# CH32V20xG8-R0.net
KiCad netlist of a schematic drawn in Altium Designer
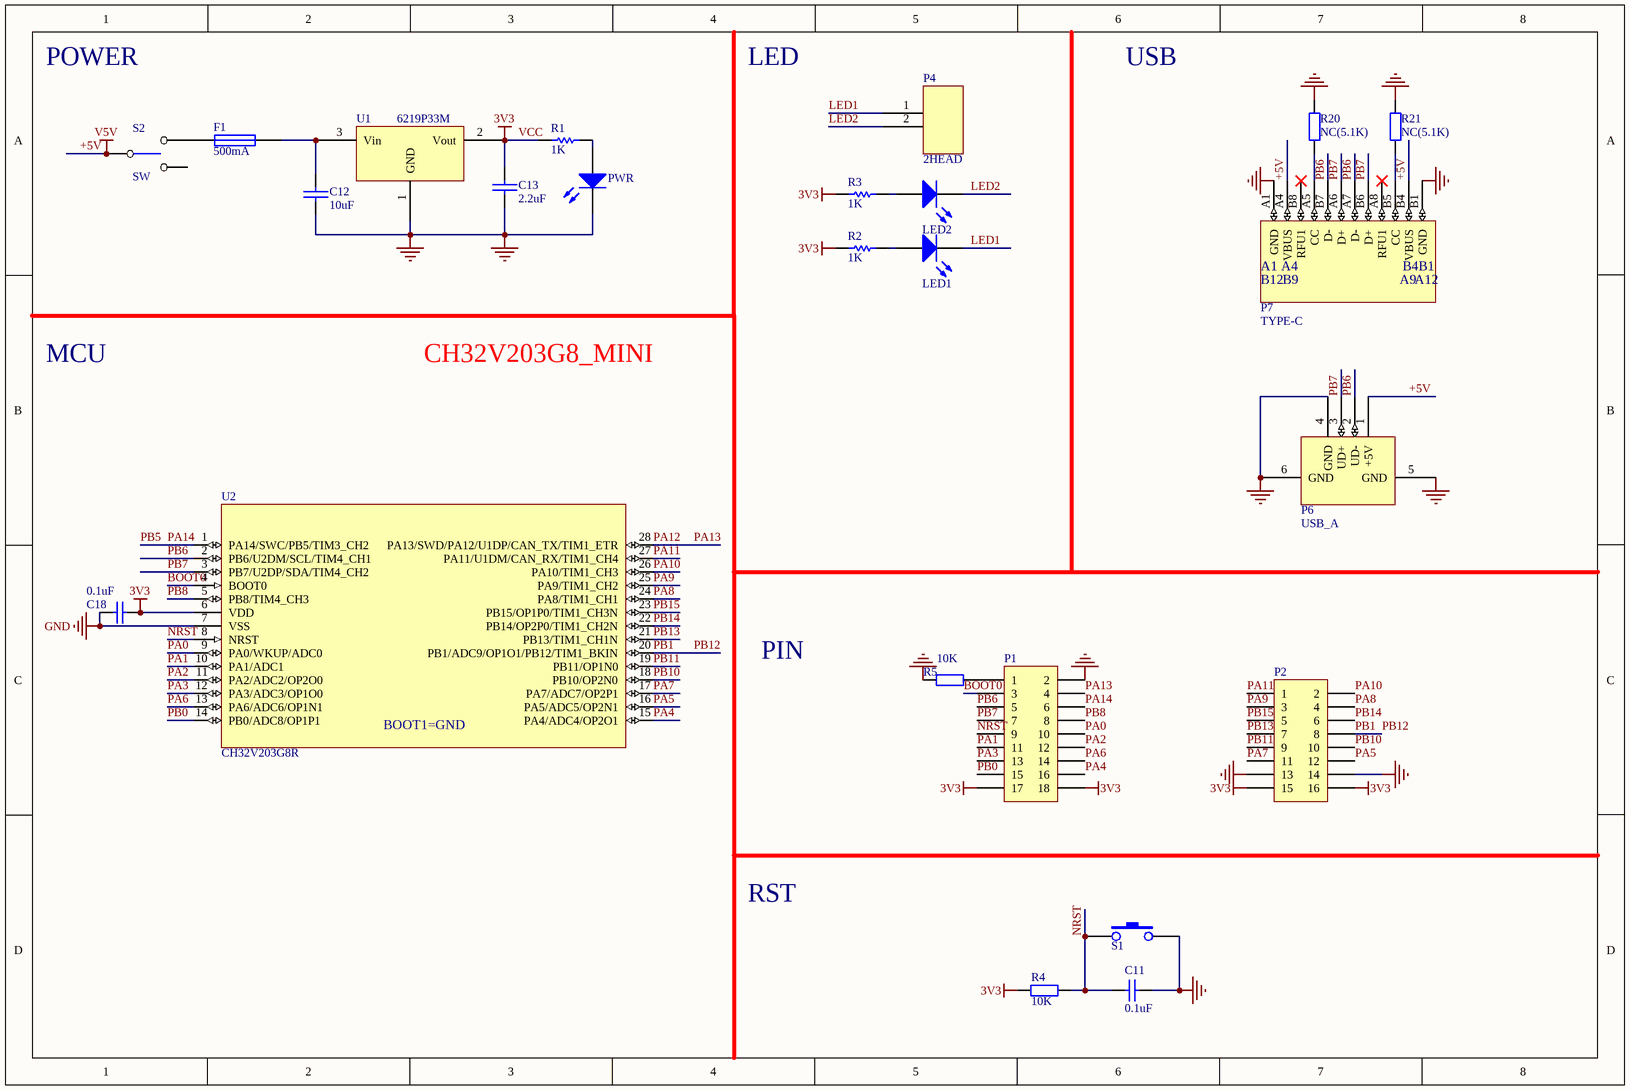
[diagram p0: CH32V20xG8-R0.SchDoc]

(export (version "E")
  (design (tool "Eeschema 10.0.6"))
  (components
    (comp (ref "C11")
      (value "0.1uF")
      (footprint "0603_C")
      (description "Capacitor")
      (fields (field (name "PUBLISHER") "Altium Limited"))
      (libsource (lib "*") (part "Cap"))
    )
    (comp (ref "C12")
      (value "10uF")
      (footprint "3216_C")
      (description "Capacitor")
      (libsource (lib "wch_sch_others") (part "CAP"))
    )
    (comp (ref "C13")
      (value "2.2uF")
      (footprint "0603_C")
      (description "Capacitor")
      (libsource (lib "wch_sch_others") (part "CAP"))
    )
    (comp (ref "C18")
      (value "0.1uF")
      (footprint "0603_C")
      (description "Capacitor")
      (fields (field (name "PUBLISHER") "Altium Limited"))
      (libsource (lib "*") (part "Cap"))
    )
    (comp (ref "F1")
      (value "500mA")
      (footprint "0603")
      (description "Fuse")
      (libsource (lib "*") (part "FUSE1"))
    )
    (comp (ref "LED1")
      (value "LED1   blue")
      (footprint "0603+")
      (description "Typical INFRARED GaAs LED")
      (fields (field (name "PUBLISHER") "Altium Limited"))
      (libsource (lib "*") (part "LED0"))
    )
    (comp (ref "LED2")
      (value "LED2  blue")
      (footprint "0603+")
      (description "Typical INFRARED GaAs LED")
      (fields (field (name "PUBLISHER") "Altium Limited"))
      (libsource (lib "*") (part "LED0"))
    )
    (comp (ref "P1")
      (value "Header 9X2")
      (footprint "IDC18-2.54mm")
      (description "Header, 9-Pin, Dual row")
      (fields (field (name "PUBLISHER") "Altium Limited"))
      (libsource (lib "Miscellaneous Connectors") (part "Header 9X2"))
    )
    (comp (ref "P2")
      (value "Header 8X2")
      (footprint "IDC16-2.54mm")
      (description "Header, 8-Pin, Dual row")
      (fields (field (name "PUBLISHER") "Altium Limited"))
      (libsource (lib "Miscellaneous Connectors") (part "Header 8X2"))
    )
    (comp (ref "P4") (value "2HEAD") (footprint "SIP2-2.54mm") (libsource (lib "*") (part "2HEAD")))
    (comp (ref "P6")
      (value "USB_A")
      (footprint "USBAF")
      (description "USB Port")
      (libsource (lib "*") (part "USB"))
    )
    (comp (ref "P7")
      (value "TYPE-C")
      (footprint "TYPE-C-Receptacle-2.0")
      (libsource (lib "*") (part "TYPE-C1"))
    )
    (comp (ref "PWR")
      (value "POWER  red")
      (footprint "0603+")
      (description "Typical INFRARED GaAs LED")
      (fields (field (name "PUBLISHER") "Altium Limited"))
      (libsource (lib "*") (part "LED0"))
    )
    (comp (ref "R1")
      (value "1K")
      (footprint "0603")
      (description "Semiconductor Resistor")
      (fields (field (name "PUBLISHER") "Altium Limited"))
      (libsource (lib "*") (part "Res Semi"))
    )
    (comp (ref "R2")
      (value "1K")
      (footprint "0603")
      (description "Semiconductor Resistor")
      (fields (field (name "PUBLISHER") "Altium Limited"))
      (libsource (lib "*") (part "Res Semi"))
    )
    (comp (ref "R3")
      (value "1K")
      (footprint "0603")
      (description "Semiconductor Resistor")
      (fields (field (name "PUBLISHER") "Altium Limited"))
      (libsource (lib "*") (part "Res Semi"))
    )
    (comp (ref "R4")
      (value "10K")
      (footprint "0603")
      (description "Resistor")
      (fields (field (name "PUBLISHER") "Altium Limited"))
      (libsource (lib "*") (part "Res2"))
    )
    (comp (ref "R5")
      (value "10K")
      (footprint "0603")
      (description "Resistor")
      (fields (field (name "PUBLISHER") "Altium Limited"))
      (libsource (lib "") (part "Res2_1"))
    )
    (comp (ref "R20")
      (value "NC(5.1K)")
      (footprint "0603")
      (description "Resistor")
      (libsource (lib "Miscellaneous Devices") (part "Res2"))
    )
    (comp (ref "R21")
      (value "NC(5.1K)")
      (footprint "0603")
      (description "Resistor")
      (libsource (lib "Miscellaneous Devices") (part "Res2"))
    )
    (comp (ref "S1") (value "NRST") (footprint "SMD_6.1x3.65x2.5mm-KEY") (libsource (lib "*") (part "KEY")))
    (comp (ref "S2") (value "SW") (footprint "KEY2") (libsource (lib "*") (part "SW")))
    (comp (ref "U1")
      (value "6219P33M")
      (footprint "SOT-23")
      (libsource (lib "wch_sch_others") (part "6219P33M"))
    )
    (comp (ref "U2")
      (value "CH32V203G8R")
      (footprint "QSOP28")
      (description "RISC-V LMD-MCU, 144MHz, for motor & wireless charging")
      (libsource (lib "CHXXX") (part "CH32V203G8R"))
    )
  )
  (nets
    (net (code "2") (name "/BOOT0") (class "Default")
      (node (ref "P1") (pin "3") (pinfunction "3_3") (pintype "passive"))
      (node (ref "U2") (pin "4") (pinfunction "BOOT0_4") (pintype "input"))
    )
    (net (code "3") (name "/LED1") (class "Default")
      (node (ref "LED1") (pin "2") (pinfunction "K_2") (pintype "passive"))
      (node (ref "P4") (pin "1") (pintype "passive"))
    )
    (net (code "4") (name "/LED2") (class "Default")
      (node (ref "LED2") (pin "2") (pinfunction "K_2") (pintype "passive"))
      (node (ref "P4") (pin "2") (pintype "passive"))
    )
    (net (code "5") (name "/NRST") (class "Default")
      (node (ref "C11") (pin "2") (pinfunction "2_2") (pintype "passive"))
      (node (ref "P1") (pin "9") (pinfunction "9_9") (pintype "passive"))
      (node (ref "R4") (pin "1") (pinfunction "1_1") (pintype "passive"))
      (node (ref "S1") (pin "1") (pinfunction "1_1") (pintype "passive"))
      (node (ref "U2") (pin "8") (pinfunction "NRST_8") (pintype "input"))
    )
    (net (code "6") (name "/PA0") (class "Default")
      (node (ref "P1") (pin "10") (pinfunction "10_10") (pintype "passive"))
      (node (ref "U2") (pin "9") (pinfunction "PA0/WKUP/ADC0_9") (pintype "bidirectional"))
    )
    (net (code "7") (name "/PA1") (class "Default")
      (node (ref "P1") (pin "11") (pinfunction "11_11") (pintype "passive"))
      (node (ref "U2") (pin "10") (pinfunction "PA1/ADC1_10") (pintype "bidirectional"))
    )
    (net (code "8") (name "/PA2") (class "Default")
      (node (ref "P1") (pin "12") (pinfunction "12_12") (pintype "passive"))
      (node (ref "U2") (pin "11") (pinfunction "PA2/ADC2/OP2O0_11") (pintype "bidirectional"))
    )
    (net (code "9") (name "/PA3") (class "Default")
      (node (ref "P1") (pin "13") (pinfunction "13_13") (pintype "passive"))
      (node (ref "U2") (pin "12") (pinfunction "PA3/ADC3/OP1O0_12") (pintype "bidirectional"))
    )
    (net (code "10") (name "/PA4") (class "Default")
      (node (ref "P1") (pin "16") (pinfunction "16_16") (pintype "passive"))
      (node (ref "U2") (pin "15") (pinfunction "PA4/ADC4/OP2O1_15") (pintype "bidirectional"))
    )
    (net (code "11") (name "/PA5") (class "Default")
      (node (ref "P2") (pin "12") (pinfunction "12_12") (pintype "passive"))
      (node (ref "U2") (pin "16") (pinfunction "PA5/ADC5/OP2N1_16") (pintype "bidirectional"))
    )
    (net (code "12") (name "/PA6") (class "Default")
      (node (ref "P1") (pin "14") (pinfunction "14_14") (pintype "passive"))
      (node (ref "U2") (pin "13") (pinfunction "PA6/ADC6/OP1N1_13") (pintype "bidirectional"))
    )
    (net (code "13") (name "/PA7") (class "Default")
      (node (ref "P2") (pin "11") (pinfunction "11_11") (pintype "passive"))
      (node (ref "U2") (pin "17") (pinfunction "PA7/ADC7/OP2P1_17") (pintype "bidirectional"))
    )
    (net (code "14") (name "/PA8") (class "Default")
      (node (ref "P2") (pin "4") (pinfunction "4_4") (pintype "passive"))
      (node (ref "U2") (pin "24") (pinfunction "PA8/TIM1_CH1_24") (pintype "bidirectional"))
    )
    (net (code "15") (name "/PA9") (class "Default")
      (node (ref "P2") (pin "3") (pinfunction "3_3") (pintype "passive"))
      (node (ref "U2") (pin "25") (pinfunction "PA9/TIM1_CH2_25") (pintype "bidirectional"))
    )
    (net (code "16") (name "/PA10") (class "Default")
      (node (ref "P2") (pin "2") (pinfunction "2_2") (pintype "passive"))
      (node (ref "U2") (pin "26") (pinfunction "PA10/TIM1_CH3_26") (pintype "bidirectional"))
    )
    (net (code "17") (name "/PA11") (class "Default")
      (node (ref "P2") (pin "1") (pinfunction "1_1") (pintype "passive"))
      (node (ref "U2") (pin "27") (pinfunction "PA11/U1DM/CAN_RX/TIM1_CH4_27") (pintype "bidirectional"))
    )
    (net (code "18") (name "/PA12") (class "Default")
      (node (ref "P1") (pin "4") (pinfunction "4_4") (pintype "passive"))
      (node (ref "U2") (pin "28") (pinfunction "PA13/SWD/PA12/U1DP/CAN_TX/TIM1_ETR_28") (pintype "bidirectional"))
    )
    (net (code "19") (name "/PA14") (class "Default")
      (node (ref "P1") (pin "6") (pinfunction "6_6") (pintype "passive"))
      (node (ref "U2") (pin "1") (pinfunction "PA14/SWC/PB5/TIM3_CH2_1") (pintype "bidirectional"))
    )
    (net (code "20") (name "/PB0") (class "Default")
      (node (ref "P1") (pin "15") (pinfunction "15_15") (pintype "passive"))
      (node (ref "U2") (pin "14") (pinfunction "PB0/ADC8/OP1P1_14") (pintype "bidirectional"))
    )
    (net (code "21") (name "/PB1") (class "Default")
      (node (ref "P2") (pin "8") (pinfunction "8_8") (pintype "passive"))
      (node (ref "U2") (pin "20") (pinfunction "PB1/ADC9/OP1O1/PB12/TIM1_BKIN_20") (pintype "bidirectional"))
    )
    (net (code "22") (name "/PB6") (class "Default")
      (node (ref "P1") (pin "5") (pinfunction "5_5") (pintype "passive"))
      (node (ref "P6") (pin "2") (pinfunction "UD-_2") (pintype "bidirectional"))
      (node (ref "P7") (pin "A7") (pinfunction "D-_A7") (pintype "bidirectional"))
      (node (ref "P7") (pin "B7") (pinfunction "D-_B7") (pintype "bidirectional"))
      (node (ref "U2") (pin "2") (pinfunction "PB6/U2DM/SCL/TIM4_CH1_2") (pintype "bidirectional"))
    )
    (net (code "23") (name "/PB7") (class "Default")
      (node (ref "P1") (pin "7") (pinfunction "7_7") (pintype "passive"))
      (node (ref "P6") (pin "3") (pinfunction "UD+_3") (pintype "bidirectional"))
      (node (ref "P7") (pin "A6") (pinfunction "D+_A6") (pintype "bidirectional"))
      (node (ref "P7") (pin "B6") (pinfunction "D+_B6") (pintype "bidirectional"))
      (node (ref "U2") (pin "3") (pinfunction "PB7/U2DP/SDA/TIM4_CH2_3") (pintype "bidirectional"))
    )
    (net (code "24") (name "/PB8") (class "Default")
      (node (ref "P1") (pin "8") (pinfunction "8_8") (pintype "passive"))
      (node (ref "U2") (pin "5") (pinfunction "PB8/TIM4_CH3_5") (pintype "bidirectional"))
    )
    (net (code "25") (name "/PB10") (class "Default")
      (node (ref "P2") (pin "10") (pinfunction "10_10") (pintype "passive"))
      (node (ref "U2") (pin "18") (pinfunction "PB10/OP2N0_18") (pintype "bidirectional"))
    )
    (net (code "26") (name "/PB11") (class "Default")
      (node (ref "P2") (pin "9") (pinfunction "9_9") (pintype "passive"))
      (node (ref "U2") (pin "19") (pinfunction "PB11/OP1N0_19") (pintype "bidirectional"))
    )
    (net (code "27") (name "/PB13") (class "Default")
      (node (ref "P2") (pin "7") (pinfunction "7_7") (pintype "passive"))
      (node (ref "U2") (pin "21") (pinfunction "PB13/TIM1_CH1N_21") (pintype "bidirectional"))
    )
    (net (code "28") (name "/PB14") (class "Default")
      (node (ref "P2") (pin "6") (pinfunction "6_6") (pintype "passive"))
      (node (ref "U2") (pin "22") (pinfunction "PB14/OP2P0/TIM1_CH2N_22") (pintype "bidirectional"))
    )
    (net (code "29") (name "/PB15") (class "Default")
      (node (ref "P2") (pin "5") (pinfunction "5_5") (pintype "passive"))
      (node (ref "U2") (pin "23") (pinfunction "PB15/OP1P0/TIM1_CH3N_23") (pintype "bidirectional"))
    )
    (net (code "30") (name "3V3") (class "Default")
      (node (ref "C13") (pin "2") (pinfunction "2_2") (pintype "passive"))
      (node (ref "C18") (pin "2") (pinfunction "2_2") (pintype "passive"))
      (node (ref "P1") (pin "17") (pinfunction "17_17") (pintype "passive"))
      (node (ref "P1") (pin "18") (pinfunction "18_18") (pintype "passive"))
      (node (ref "P2") (pin "15") (pinfunction "15_15") (pintype "passive"))
      (node (ref "P2") (pin "16") (pinfunction "16_16") (pintype "passive"))
      (node (ref "R1") (pin "2") (pinfunction "2_2") (pintype "passive"))
      (node (ref "R2") (pin "1") (pinfunction "1_1") (pintype "passive"))
      (node (ref "R3") (pin "1") (pinfunction "1_1") (pintype "passive"))
      (node (ref "R4") (pin "2") (pinfunction "2_2") (pintype "passive"))
      (node (ref "U1") (pin "2") (pinfunction "Vout_2") (pintype "passive"))
      (node (ref "U2") (pin "6") (pinfunction "VDD_6") (pintype "power_in"))
    )
    (net (code "31") (name "GND") (class "Default")
      (node (ref "C11") (pin "1") (pinfunction "1_1") (pintype "passive"))
      (node (ref "C12") (pin "2") (pinfunction "2_2") (pintype "passive"))
      (node (ref "C13") (pin "1") (pinfunction "1_1") (pintype "passive"))
      (node (ref "C18") (pin "1") (pinfunction "1_1") (pintype "passive"))
      (node (ref "P1") (pin "2") (pinfunction "2_2") (pintype "passive"))
      (node (ref "P2") (pin "13") (pinfunction "13_13") (pintype "passive"))
      (node (ref "P2") (pin "14") (pinfunction "14_14") (pintype "passive"))
      (node (ref "P6") (pin "4") (pinfunction "GND_4") (pintype "power_in"))
      (node (ref "P6") (pin "5") (pinfunction "GND_5") (pintype "power_in"))
      (node (ref "P6") (pin "6") (pinfunction "GND_6") (pintype "power_in"))
      (node (ref "P7") (pin "A1") (pinfunction "GND_A1") (pintype "bidirectional"))
      (node (ref "P7") (pin "B1") (pinfunction "GND_B1") (pintype "bidirectional"))
      (node (ref "PWR") (pin "2") (pinfunction "K_2") (pintype "passive"))
      (node (ref "R20") (pin "2") (pinfunction "2_2") (pintype "passive"))
      (node (ref "R21") (pin "2") (pinfunction "2_2") (pintype "passive"))
      (node (ref "R5") (pin "1") (pinfunction "1_1") (pintype "passive"))
      (node (ref "S1") (pin "2") (pinfunction "2_2") (pintype "passive"))
      (node (ref "U1") (pin "1") (pinfunction "GND_1") (pintype "passive"))
      (node (ref "U2") (pin "7") (pinfunction "VSS_7") (pintype "power_in"))
    )
    (net (code "32") (name "Net-(F1-Pad1)") (class "Default")
      (node (ref "F1") (pin "1") (pinfunction "1_1") (pintype "passive"))
      (node (ref "S2") (pin "3") (pinfunction "3_3") (pintype "passive"))
    )
    (net (code "33") (name "Net-(LED1-A)") (class "Default")
      (node (ref "LED1") (pin "1") (pinfunction "A_1") (pintype "passive"))
      (node (ref "R2") (pin "2") (pinfunction "2_2") (pintype "passive"))
    )
    (net (code "34") (name "Net-(LED2-A)") (class "Default")
      (node (ref "LED2") (pin "1") (pinfunction "A_1") (pintype "passive"))
      (node (ref "R3") (pin "2") (pinfunction "2_2") (pintype "passive"))
    )
    (net (code "35") (name "Net-(P1-Pad1)") (class "Default")
      (node (ref "P1") (pin "1") (pinfunction "1_1") (pintype "passive"))
      (node (ref "R5") (pin "2") (pinfunction "2_2") (pintype "passive"))
    )
    (net (code "36") (name "Net-(P7-CC-PadA5)") (class "Default")
      (node (ref "P7") (pin "A5") (pinfunction "CC_A5") (pintype "bidirectional"))
      (node (ref "R20") (pin "1") (pinfunction "1_1") (pintype "passive"))
    )
    (net (code "37") (name "Net-(P7-CC-PadB5)") (class "Default")
      (node (ref "P7") (pin "B5") (pinfunction "CC_B5") (pintype "bidirectional"))
      (node (ref "R21") (pin "1") (pinfunction "1_1") (pintype "passive"))
    )
    (net (code "38") (name "Net-(PWR-A)") (class "Default")
      (node (ref "PWR") (pin "1") (pinfunction "A_1") (pintype "passive"))
      (node (ref "R1") (pin "1") (pinfunction "1_1") (pintype "passive"))
    )
    (net (code "39") (name "Net-(U1-Vin)") (class "Default")
      (node (ref "C12") (pin "1") (pinfunction "1_1") (pintype "passive"))
      (node (ref "F1") (pin "2") (pinfunction "2_2") (pintype "passive"))
      (node (ref "U1") (pin "3") (pinfunction "Vin_3") (pintype "passive"))
    )
    (net (code "40") (name "V5V") (class "Default")
      (node (ref "P6") (pin "1") (pinfunction "+5V_1") (pintype "power_in"))
      (node (ref "P7") (pin "A4") (pinfunction "VBUS_A4") (pintype "bidirectional"))
      (node (ref "P7") (pin "B4") (pinfunction "VBUS_B4") (pintype "bidirectional"))
      (node (ref "S2") (pin "1") (pinfunction "1_1") (pintype "passive"))
    )
    (net (code "41") (name "unconnected-(P7-RFU1-PadA8)") (class "Default")
      (node (ref "P7") (pin "A8") (pinfunction "RFU1_A8") (pintype "bidirectional+no_connect"))
    )
    (net (code "42") (name "unconnected-(P7-RFU1-PadB8)") (class "Default")
      (node (ref "P7") (pin "B8") (pinfunction "RFU1_B8") (pintype "bidirectional+no_connect"))
    )
    (net (code "43") (name "unconnected-(S2-Pad2)") (class "Default")
      (node (ref "S2") (pin "2") (pinfunction "2_2") (pintype "passive"))
    )
  )
)
